# schematics_easyEDA.net
KiCad netlist of a schematic drawn in EasyEDA
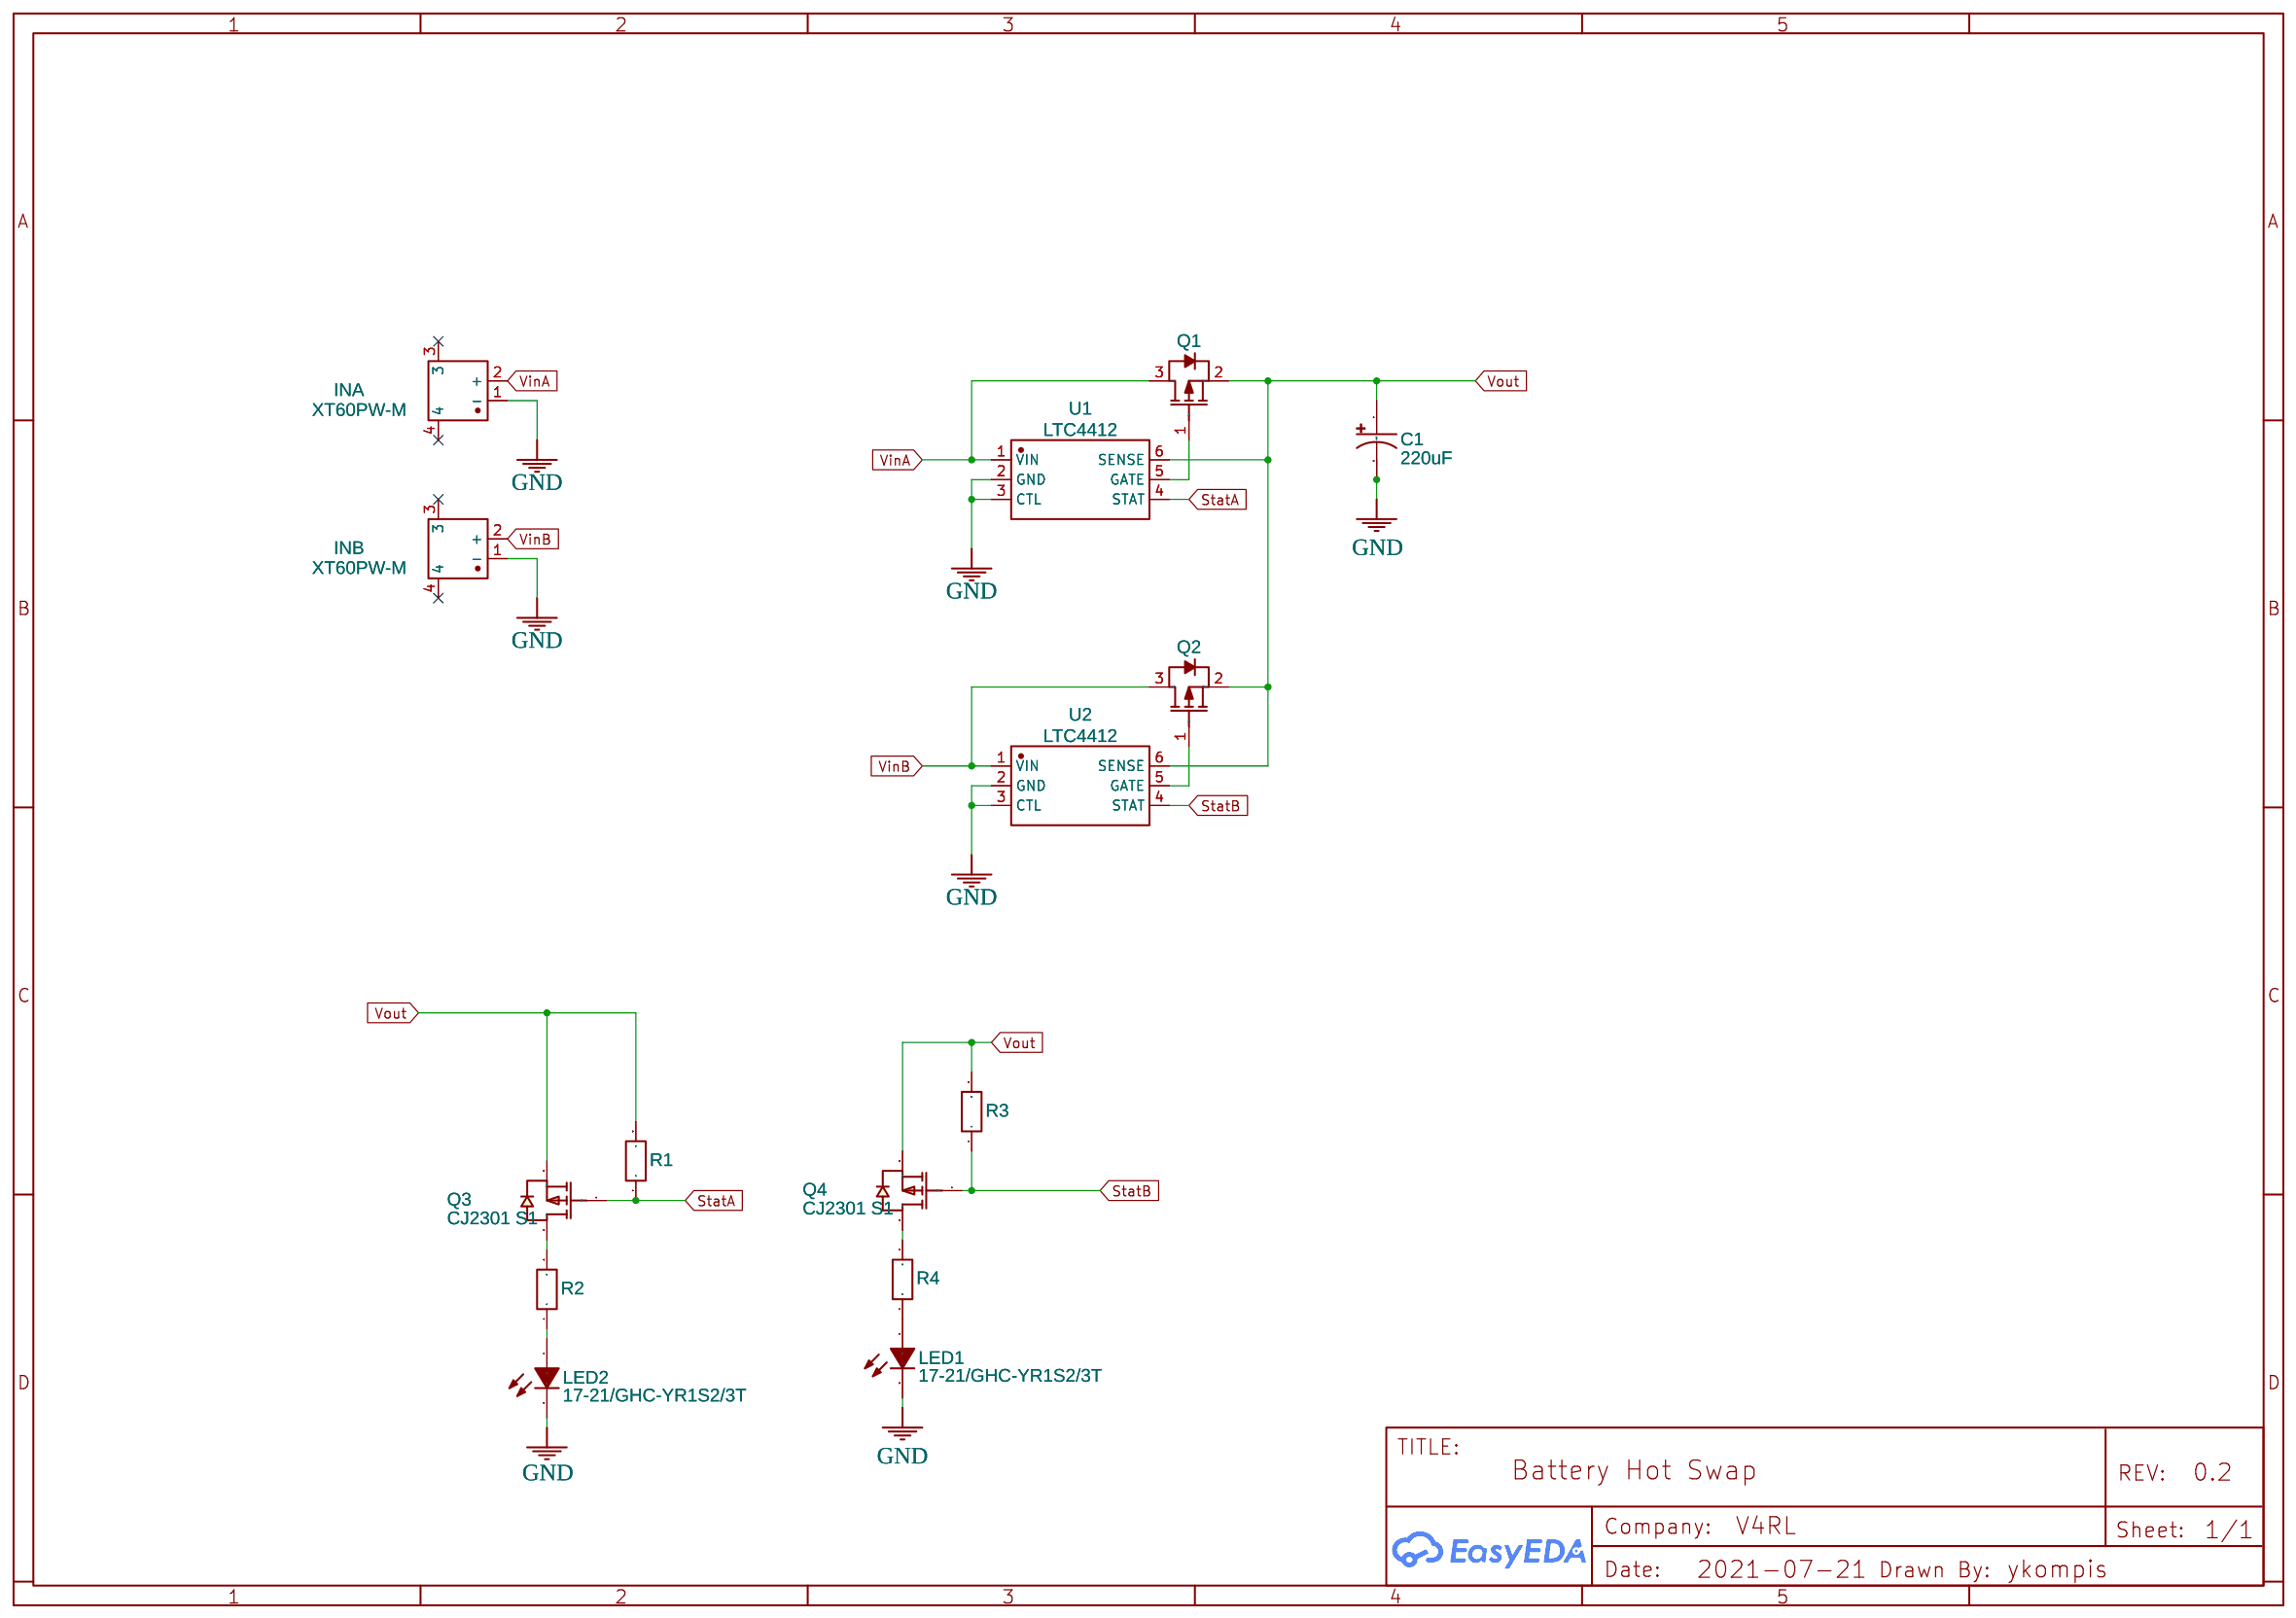
[diagram p0: Battery Hot Swap]
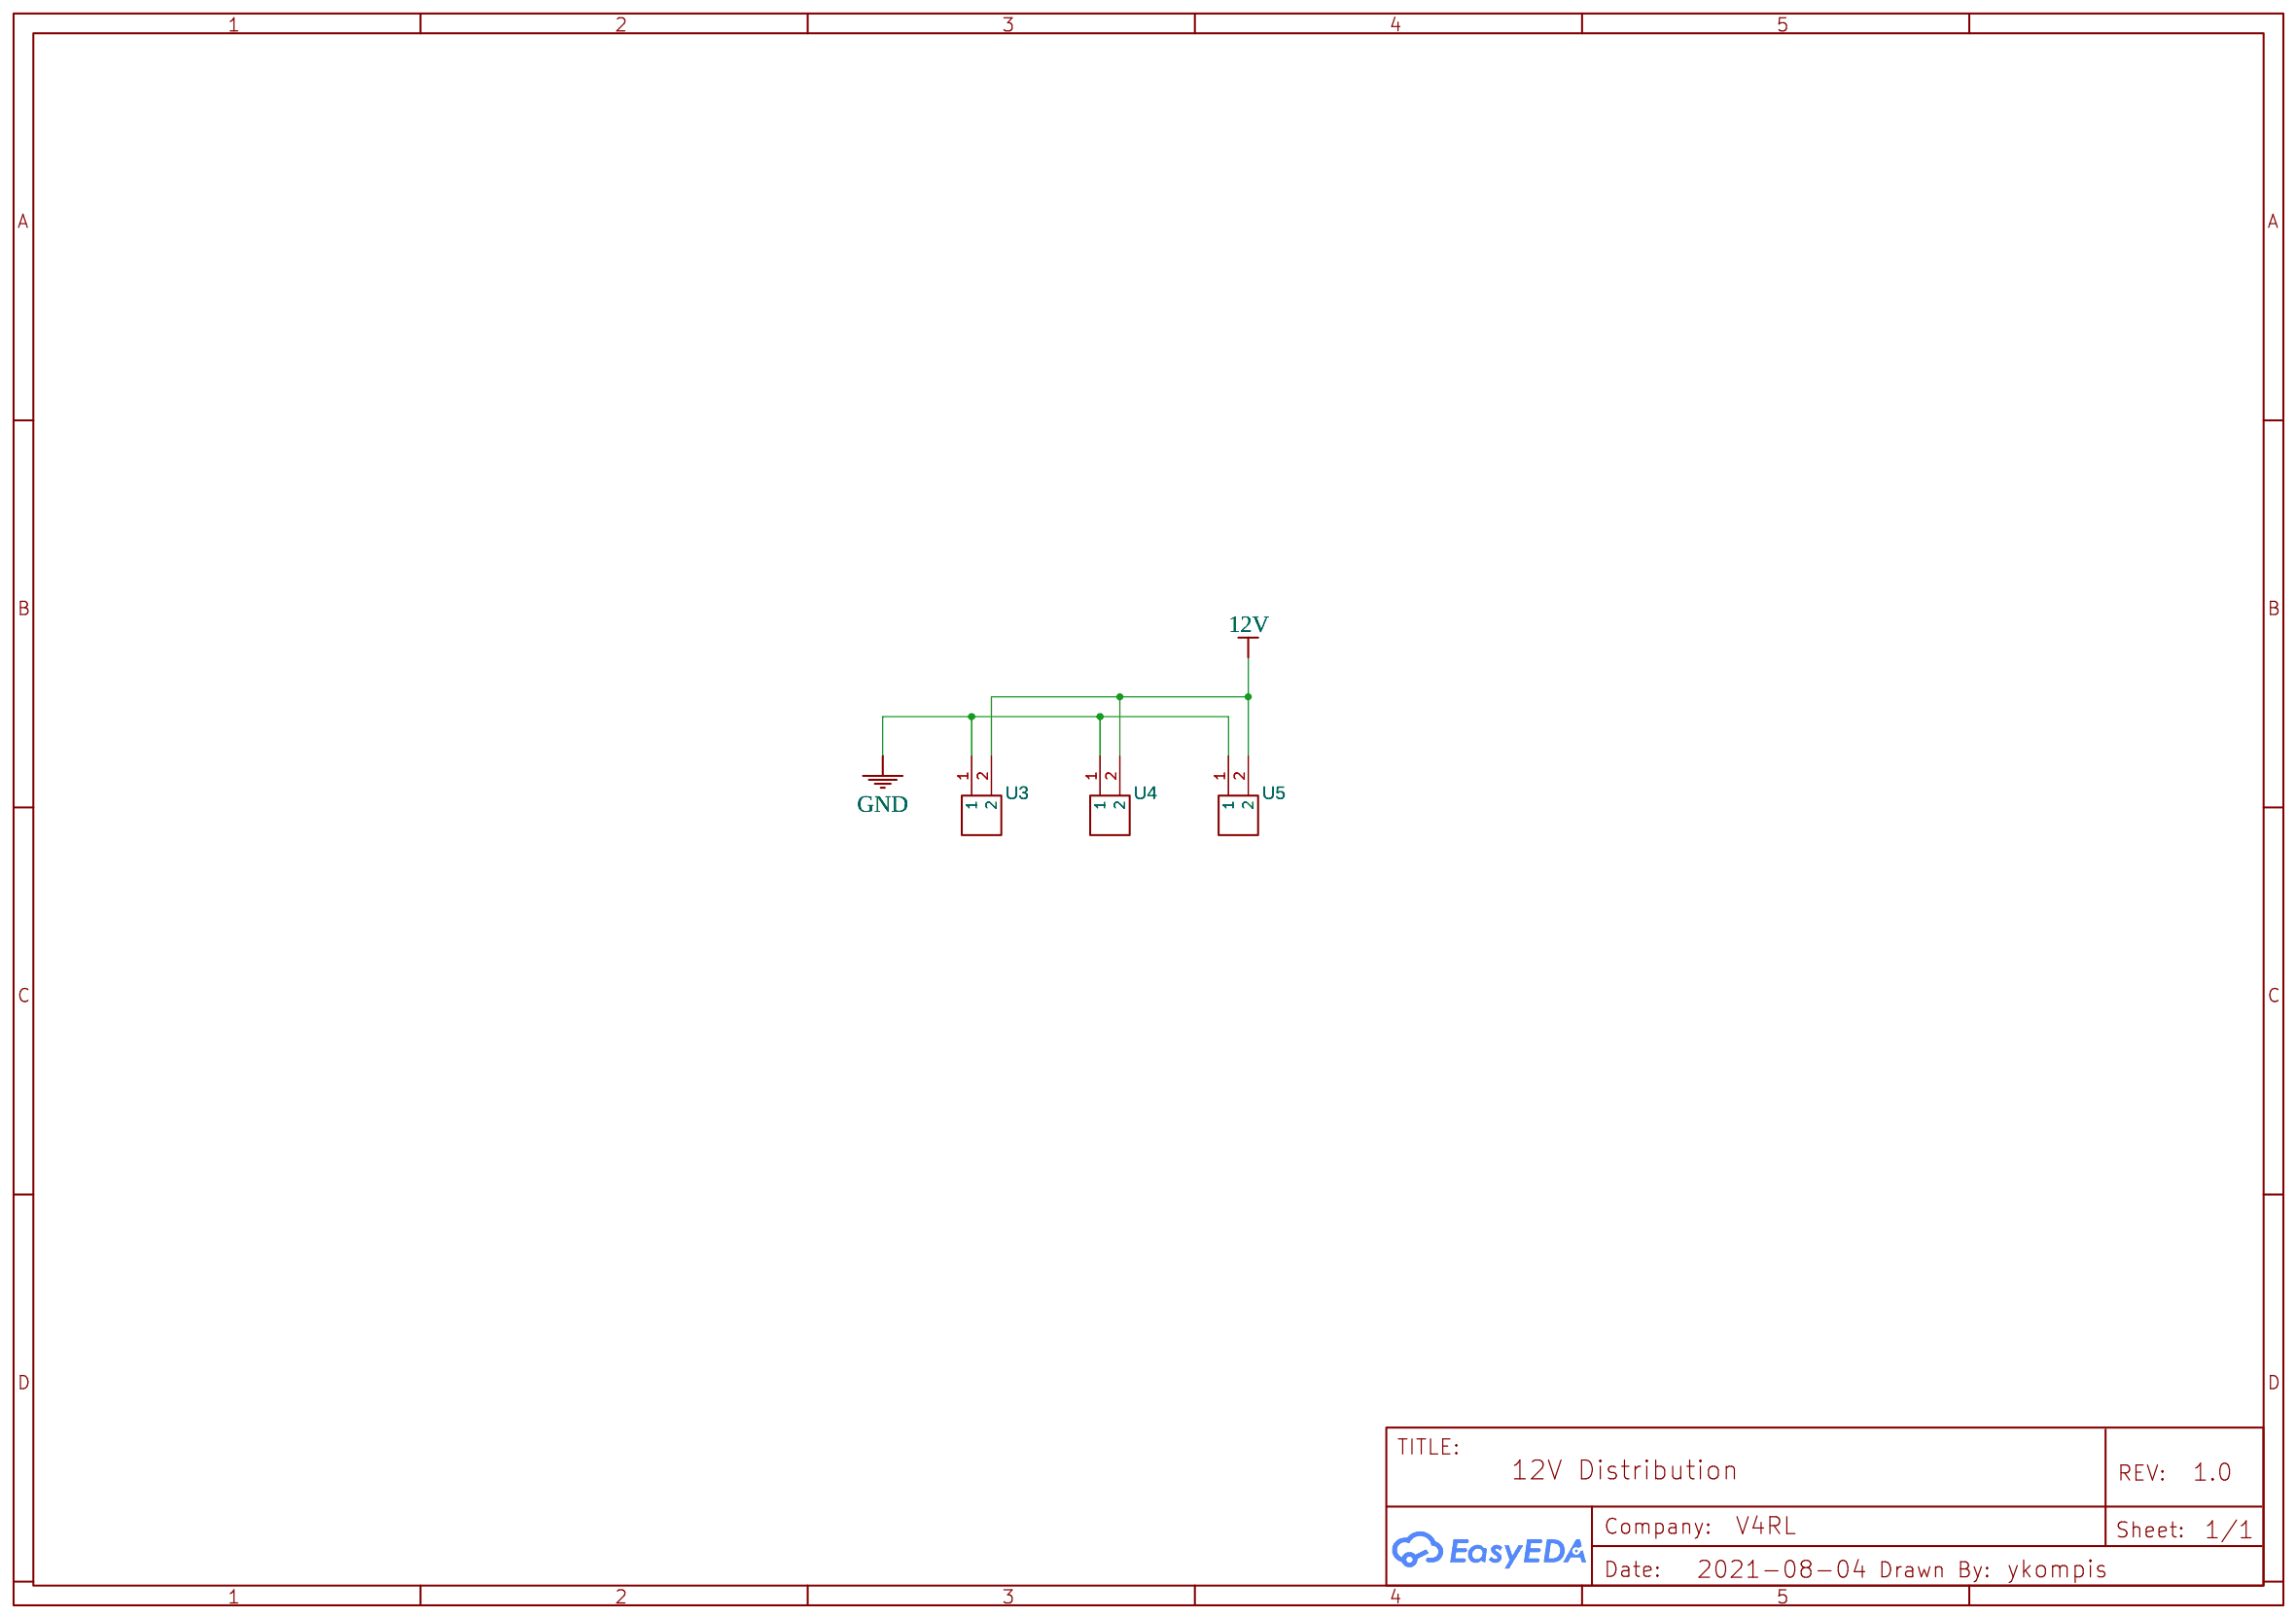
[diagram p1: 12V Distribution]

(export (version "E")
  (design (tool "Eeschema 10.0.6"))
  (components
    (comp (ref "C1")
      (value "220uF")
      (fields
        (field (name "BOM_Manufacturer Part") "EEEFC1V221AP")
        (field (name "BOM_Supplier Part") "C401627")
      )
      (libsource (lib "") (part "EEEFC1V221AP"))
    )
    (comp (ref "INA")
      (value "XT60PW-M")
      (fields (field (name "BOM_Supplier Part") "C98732"))
      (libsource (lib "") (part "XT60PW-M"))
    )
    (comp (ref "INB")
      (value "XT60PW-M")
      (fields (field (name "BOM_Supplier Part") "C98732"))
      (libsource (lib "") (part "XT60PW-M_1"))
    )
    (comp (ref "LED1")
      (value "17-21/GHC-YR1S2/3T")
      (fields (field (name "BOM_Supplier Part") "C73546"))
      (libsource (lib "") (part "17-21/GHC-YR1S2/3T"))
    )
    (comp (ref "LED2")
      (value "17-21/GHC-YR1S2/3T")
      (fields (field (name "BOM_Supplier Part") "C73546"))
      (libsource (lib "") (part "17-21/GHC-YR1S2/3T"))
    )
    (comp (ref "Q1")
      (value "FDD4685")
      (fields (field (name "BOM_Supplier Part") "C258227"))
      (libsource (lib "") (part "FDD4685"))
    )
    (comp (ref "Q2")
      (value "FDD4685")
      (fields (field (name "BOM_Supplier Part") "C258227"))
      (libsource (lib "") (part "FDD4685"))
    )
    (comp (ref "Q3")
      (value "CJ2301 S1")
      (fields (field (name "BOM_Supplier Part") "C8547"))
      (libsource (lib "") (part "CJ2301 S1"))
    )
    (comp (ref "Q4")
      (value "CJ2301 S1")
      (fields (field (name "BOM_Supplier Part") "C8547"))
      (libsource (lib "") (part "CJ2301 S1"))
    )
    (comp (ref "R1")
      (value "ARG05DTC1000")
      (fields (field (name "BOM_Supplier Part") "C1509658"))
      (libsource (lib "") (part "ARG05DTC1000"))
    )
    (comp (ref "R2")
      (value "ARG05DTC1000")
      (fields (field (name "BOM_Supplier Part") "C1509658"))
      (libsource (lib "") (part "ARG05DTC1000"))
    )
    (comp (ref "R3")
      (value "ARG05DTC1000")
      (fields (field (name "BOM_Supplier Part") "C1509658"))
      (libsource (lib "") (part "ARG05DTC1000"))
    )
    (comp (ref "R4")
      (value "ARG05DTC1000")
      (fields (field (name "BOM_Supplier Part") "C1509658"))
      (libsource (lib "") (part "ARG05DTC1000"))
    )
    (comp (ref "U1")
      (value "LTC4412")
      (fields
        (field (name "BOM_Manufacturer Part") "LTC4412ES6#TRPBF")
        (field (name "BOM_Supplier Part") "C514442")
      )
      (libsource (lib "") (part "LTC4412ES6#TRPBF"))
    )
    (comp (ref "U2")
      (value "LTC4412")
      (fields
        (field (name "BOM_Manufacturer Part") "LTC4412ES6#TRPBF")
        (field (name "BOM_Supplier Part") "C514442")
      )
      (libsource (lib "") (part "LTC4412ES6#TRPBF"))
    )
    (comp (ref "U3") (value "MOLEX 430450200") (libsource (lib "") (part "MOLEX 430450200")))
    (comp (ref "U4") (value "MOLEX 430450200") (libsource (lib "") (part "MOLEX 430450200")))
    (comp (ref "U5") (value "MOLEX 430450200") (libsource (lib "") (part "MOLEX 430450200")))
  )
  (nets
    (net (code "1") (name "12V") (class "Default")
      (node (ref "U3") (pin "2") (pinfunction "2_2") (pintype "unspecified"))
      (node (ref "U4") (pin "2") (pinfunction "2_2") (pintype "unspecified"))
      (node (ref "U5") (pin "2") (pinfunction "2_2") (pintype "unspecified"))
    )
    (net (code "2") (name "GND") (class "Default")
      (node (ref "C1") (pin "2") (pinfunction "2_2") (pintype "unspecified"))
      (node (ref "INA") (pin "1") (pinfunction "-_1") (pintype "unspecified"))
      (node (ref "INB") (pin "1") (pinfunction "-_1") (pintype "unspecified"))
      (node (ref "LED1") (pin "2") (pinfunction "-_2") (pintype "input"))
      (node (ref "LED2") (pin "2") (pinfunction "-_2") (pintype "input"))
      (node (ref "U1") (pin "2") (pinfunction "GND_2") (pintype "unspecified"))
      (node (ref "U1") (pin "3") (pinfunction "CTL_3") (pintype "unspecified"))
      (node (ref "U2") (pin "2") (pinfunction "GND_2") (pintype "unspecified"))
      (node (ref "U2") (pin "3") (pinfunction "CTL_3") (pintype "unspecified"))
      (node (ref "U3") (pin "1") (pinfunction "1_1") (pintype "unspecified"))
      (node (ref "U4") (pin "1") (pinfunction "1_1") (pintype "unspecified"))
      (node (ref "U5") (pin "1") (pinfunction "1_1") (pintype "unspecified"))
    )
    (net (code "3") (name "Net-(LED1-+)") (class "Default")
      (node (ref "LED1") (pin "1") (pinfunction "+_1") (pintype "input"))
      (node (ref "R4") (pin "1") (pinfunction "1_1") (pintype "unspecified"))
    )
    (net (code "4") (name "Net-(LED2-+)") (class "Default")
      (node (ref "LED2") (pin "1") (pinfunction "+_1") (pintype "input"))
      (node (ref "R2") (pin "1") (pinfunction "1_1") (pintype "unspecified"))
    )
    (net (code "5") (name "Net-(Q1-G)") (class "Default")
      (node (ref "Q1") (pin "1") (pinfunction "G_1") (pintype "unspecified"))
      (node (ref "U1") (pin "5") (pinfunction "GATE_5") (pintype "unspecified"))
    )
    (net (code "6") (name "Net-(Q2-G)") (class "Default")
      (node (ref "Q2") (pin "1") (pinfunction "G_1") (pintype "unspecified"))
      (node (ref "U2") (pin "5") (pinfunction "GATE_5") (pintype "unspecified"))
    )
    (net (code "7") (name "Net-(Q3-D)") (class "Default")
      (node (ref "Q3") (pin "3") (pinfunction "D_3") (pintype "unspecified"))
      (node (ref "R2") (pin "2") (pinfunction "2_2") (pintype "unspecified"))
    )
    (net (code "8") (name "Net-(Q4-D)") (class "Default")
      (node (ref "Q4") (pin "3") (pinfunction "D_3") (pintype "unspecified"))
      (node (ref "R4") (pin "2") (pinfunction "2_2") (pintype "unspecified"))
    )
    (net (code "9") (name "StatA") (class "Default")
      (node (ref "Q3") (pin "1") (pinfunction "G_1") (pintype "unspecified"))
      (node (ref "R1") (pin "1") (pinfunction "1_1") (pintype "unspecified"))
      (node (ref "U1") (pin "4") (pinfunction "STAT_4") (pintype "unspecified"))
    )
    (net (code "10") (name "StatB") (class "Default")
      (node (ref "Q4") (pin "1") (pinfunction "G_1") (pintype "unspecified"))
      (node (ref "R3") (pin "1") (pinfunction "1_1") (pintype "unspecified"))
      (node (ref "U2") (pin "4") (pinfunction "STAT_4") (pintype "unspecified"))
    )
    (net (code "11") (name "VinA") (class "Default")
      (node (ref "INA") (pin "2") (pinfunction "+_2") (pintype "unspecified"))
      (node (ref "Q1") (pin "3") (pinfunction "D_3") (pintype "unspecified"))
      (node (ref "U1") (pin "1") (pinfunction "VIN_1") (pintype "unspecified"))
    )
    (net (code "12") (name "VinB") (class "Default")
      (node (ref "INB") (pin "2") (pinfunction "+_2") (pintype "unspecified"))
      (node (ref "Q2") (pin "3") (pinfunction "D_3") (pintype "unspecified"))
      (node (ref "U2") (pin "1") (pinfunction "VIN_1") (pintype "unspecified"))
    )
    (net (code "13") (name "Vout") (class "Default")
      (node (ref "C1") (pin "1") (pinfunction "1_1") (pintype "unspecified"))
      (node (ref "Q1") (pin "2") (pinfunction "S_2") (pintype "unspecified"))
      (node (ref "Q2") (pin "2") (pinfunction "S_2") (pintype "unspecified"))
      (node (ref "Q3") (pin "2") (pinfunction "S_2") (pintype "unspecified"))
      (node (ref "Q4") (pin "2") (pinfunction "S_2") (pintype "unspecified"))
      (node (ref "R1") (pin "2") (pinfunction "2_2") (pintype "unspecified"))
      (node (ref "R3") (pin "2") (pinfunction "2_2") (pintype "unspecified"))
      (node (ref "U1") (pin "6") (pinfunction "SENSE_6") (pintype "unspecified"))
      (node (ref "U2") (pin "6") (pinfunction "SENSE_6") (pintype "unspecified"))
    )
    (net (code "14") (name "unconnected-(INA-Pad3)") (class "Default")
      (node (ref "INA") (pin "3") (pinfunction "3_3") (pintype "unspecified+no_connect"))
    )
    (net (code "15") (name "unconnected-(INA-Pad4)") (class "Default")
      (node (ref "INA") (pin "4") (pinfunction "4_4") (pintype "unspecified+no_connect"))
    )
    (net (code "16") (name "unconnected-(INB-Pad3)") (class "Default")
      (node (ref "INB") (pin "3") (pinfunction "3_3") (pintype "unspecified+no_connect"))
    )
    (net (code "17") (name "unconnected-(INB-Pad4)") (class "Default")
      (node (ref "INB") (pin "4") (pinfunction "4_4") (pintype "unspecified+no_connect"))
    )
  )
)
